# BandpassedGainAmpThruhole.net
KiCad netlist of a schematic drawn in EAGLE
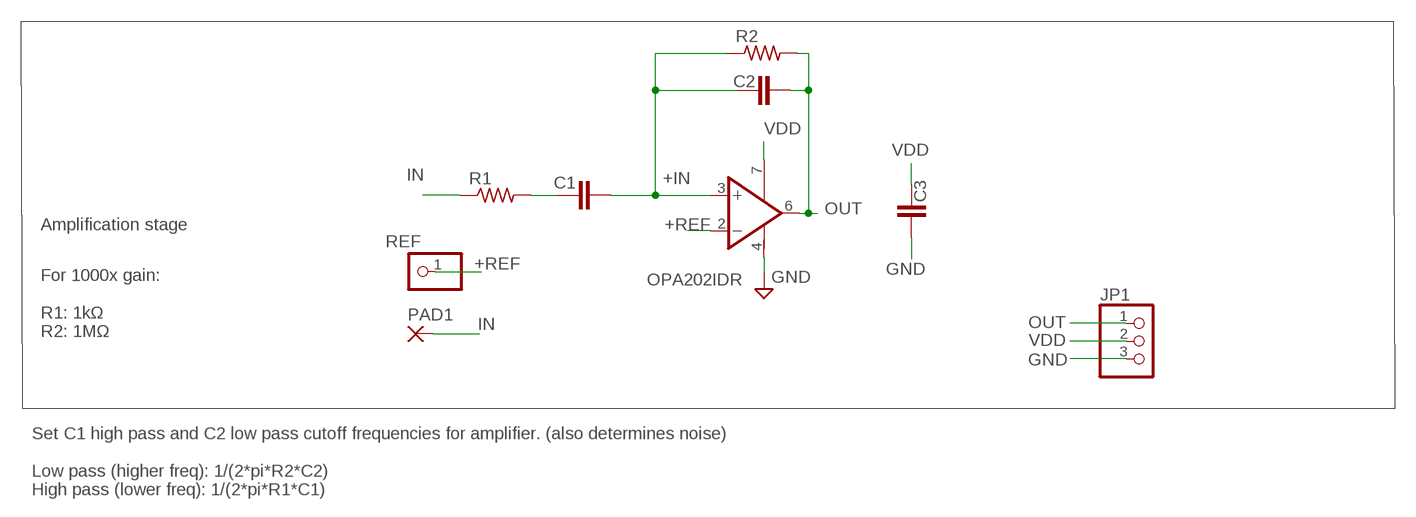
[diagram p0: schematic, sheet 1]

(export (version "E")
  (design (tool "Eeschema 10.0.6"))
  (components
    (comp (ref "C1")
      (value "C2.5/2")
      (footprint "eagle-import:C2.5-2")
      (libsource (lib "eagle-import") (part "C2.5/2"))
    )
    (comp (ref "C2")
      (value "C2.5/2")
      (footprint "eagle-import:C2.5-2")
      (libsource (lib "eagle-import") (part "C2.5/2"))
    )
    (comp (ref "C3")
      (value "C2.5/2")
      (footprint "eagle-import:C2.5-2")
      (libsource (lib "eagle-import") (part "C2.5/2"))
    )
    (comp (ref "JP1")
      (value "PINHD-1X3")
      (footprint "eagle-import:1X03")
      (libsource (lib "eagle-import") (part "PINHD-1X3"))
    )
    (comp (ref "PAD1")
      (value "3,17/1,1")
      (footprint "eagle-import:3,17_1,1")
      (libsource (lib "eagle-import") (part "3,17/1,1"))
    )
    (comp (ref "R1")
      (value "R-US_0204/5")
      (footprint "eagle-import:0204_5")
      (libsource (lib "eagle-import") (part "R-US_0204/5"))
    )
    (comp (ref "R2")
      (value "R-US_0204/5")
      (footprint "eagle-import:0204_5")
      (libsource (lib "eagle-import") (part "R-US_0204/5"))
    )
    (comp (ref "REF")
      (value "PINHD-1X1")
      (footprint "eagle-import:1X01")
      (libsource (lib "eagle-import") (part "PINHD-1X1"))
    )
    (comp (ref "U1")
      (value "OPA202IDR")
      (footprint "eagle-import:SOIC127P600X175-8N")
      (fields (field (name "MF") "Texas Instruments"))
      (libsource (lib "eagle-import") (part "OPA202IDR"))
    )
  )
  (nets
    (net (code "1") (name "/+IN") (class "Default")
      (node (ref "C1") (pin "2") (pinfunction "2_2") (pintype "passive"))
      (node (ref "C2") (pin "1") (pinfunction "1_1") (pintype "passive"))
      (node (ref "R2") (pin "1") (pinfunction "1_1") (pintype "passive"))
      (node (ref "U1") (pin "3") (pinfunction "+IN_3") (pintype "input"))
    )
    (net (code "2") (name "/+REF") (class "Default")
      (node (ref "REF") (pin "1") (pinfunction "1_1") (pintype "passive"))
      (node (ref "U1") (pin "2") (pinfunction "-IN_2") (pintype "input"))
    )
    (net (code "3") (name "/IN") (class "Default")
      (node (ref "PAD1") (pin "1") (pinfunction "P_1") (pintype "passive"))
      (node (ref "R1") (pin "1") (pinfunction "1_1") (pintype "passive"))
    )
    (net (code "4") (name "/OUT") (class "Default")
      (node (ref "C2") (pin "2") (pinfunction "2_2") (pintype "passive"))
      (node (ref "JP1") (pin "1") (pinfunction "1_1") (pintype "passive"))
      (node (ref "R2") (pin "2") (pinfunction "2_2") (pintype "passive"))
      (node (ref "U1") (pin "6") (pinfunction "OUT_6") (pintype "output"))
    )
    (net (code "5") (name "/VDD") (class "Default")
      (node (ref "C3") (pin "1") (pinfunction "1_1") (pintype "passive"))
      (node (ref "JP1") (pin "2") (pinfunction "2_2") (pintype "passive"))
      (node (ref "U1") (pin "7") (pinfunction "V+_7") (pintype "power_in"))
    )
    (net (code "6") (name "GND") (class "Default")
      (node (ref "C3") (pin "2") (pinfunction "2_2") (pintype "passive"))
      (node (ref "JP1") (pin "3") (pinfunction "3_3") (pintype "passive"))
      (node (ref "U1") (pin "4") (pinfunction "V-_4") (pintype "power_in"))
    )
    (net (code "7") (name "Net-(C1-Pad1)") (class "Default")
      (node (ref "C1") (pin "1") (pinfunction "1_1") (pintype "passive"))
      (node (ref "R1") (pin "2") (pinfunction "2_2") (pintype "passive"))
    )
  )
)
